# mpu6050schem.net
KiCad netlist of a schematic drawn in EAGLE
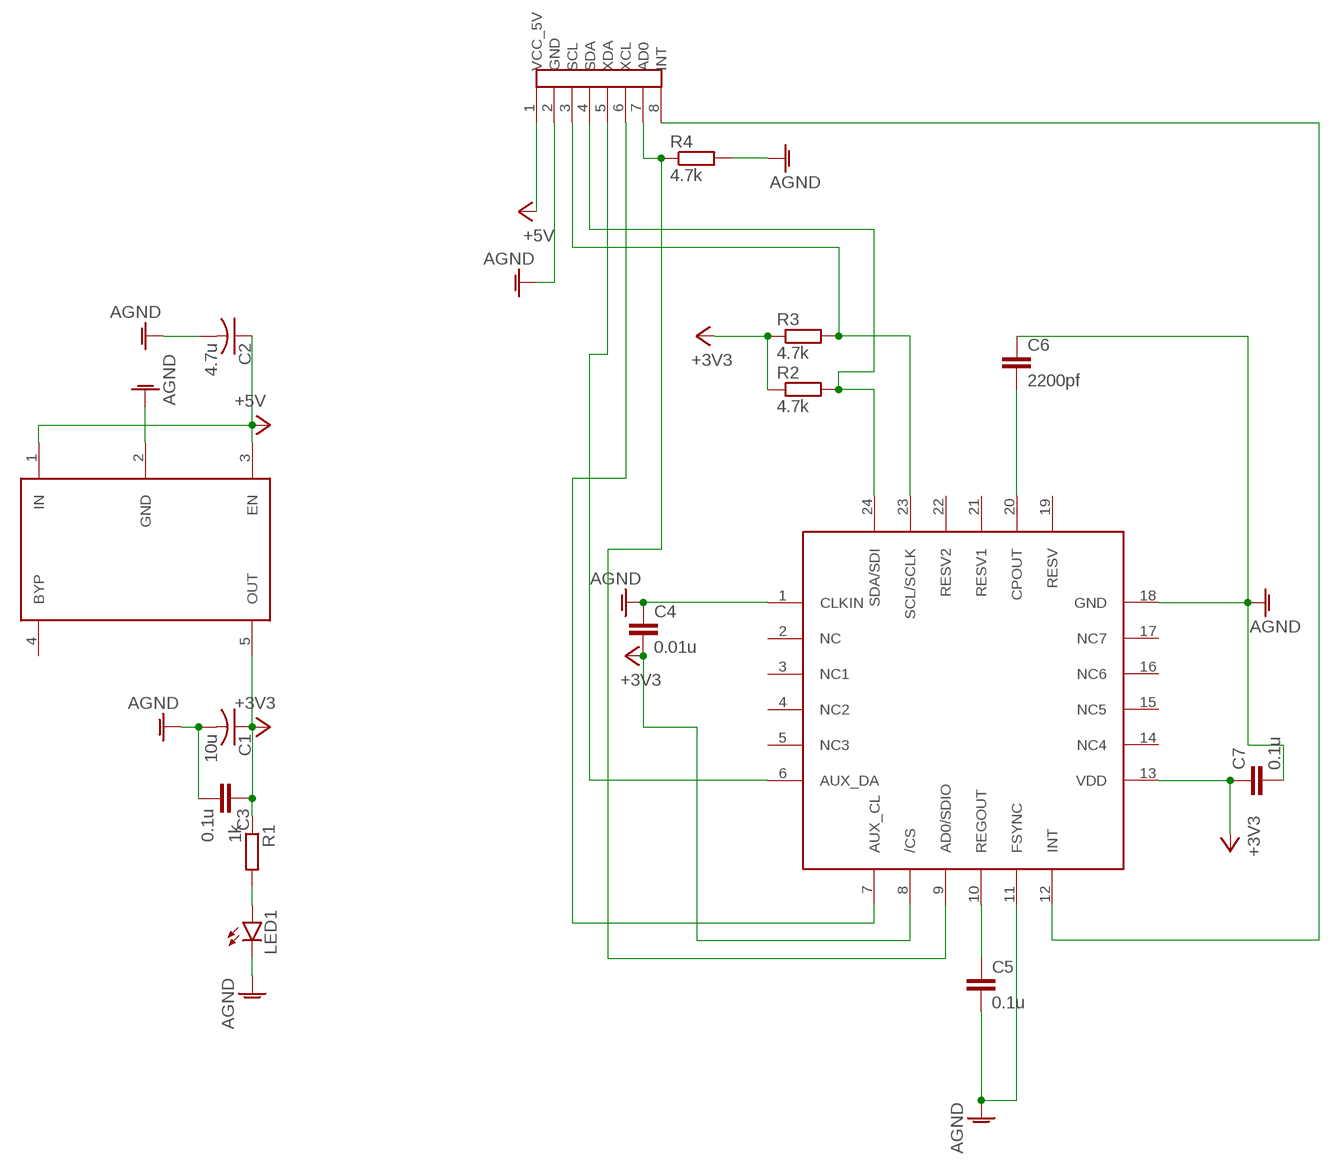
[diagram p0: schematic, sheet 1]

(export (version "E")
  (design (tool "Eeschema 10.0.6"))
  (components
    (comp (ref "C1")
      (value "10u")
      (footprint "eagle-import:C0603")
      (libsource (lib "eagle-import") (part "C-USC0603"))
    )
    (comp (ref "C2")
      (value "4.7u")
      (footprint "eagle-import:C0603")
      (libsource (lib "eagle-import") (part "C-USC0603"))
    )
    (comp (ref "C3")
      (value "0.1u")
      (footprint "eagle-import:C0402")
      (libsource (lib "eagle-import") (part "C-EUC0402"))
    )
    (comp (ref "C4")
      (value "0.01u")
      (footprint "eagle-import:C0402")
      (libsource (lib "eagle-import") (part "C-EUC0402"))
    )
    (comp (ref "C5")
      (value "0.1u")
      (footprint "eagle-import:C0402")
      (libsource (lib "eagle-import") (part "C-EUC0402"))
    )
    (comp (ref "C6")
      (value "2200pf")
      (footprint "eagle-import:C0402")
      (libsource (lib "eagle-import") (part "C-EUC0402"))
    )
    (comp (ref "C7")
      (value "0.1u")
      (footprint "eagle-import:C0402")
      (libsource (lib "eagle-import") (part "C-EUC0402"))
    )
    (comp (ref "LDO3.3V")
      (value "MIC5219")
      (footprint "eagle-import:SOT95P295X145-5N")
      (libsource (lib "eagle-import") (part "MIC5219"))
    )
    (comp (ref "LED1")
      (value "LEDCHIP-LED0603")
      (footprint "eagle-import:CHIP-LED0603")
      (libsource (lib "eagle-import") (part "LEDCHIP-LED0603"))
    )
    (comp (ref "R1")
      (value "1k")
      (footprint "eagle-import:R0402")
      (libsource (lib "eagle-import") (part "R-EU_R0402"))
    )
    (comp (ref "R2")
      (value "4.7k")
      (footprint "eagle-import:R0402")
      (libsource (lib "eagle-import") (part "R-EU_R0402"))
    )
    (comp (ref "R3")
      (value "4.7k")
      (footprint "eagle-import:R0402")
      (libsource (lib "eagle-import") (part "R-EU_R0402"))
    )
    (comp (ref "R4")
      (value "4.7k")
      (footprint "eagle-import:R0402")
      (libsource (lib "eagle-import") (part "R-EU_R0402"))
    )
    (comp (ref "U$1")
      (value "MPU6050")
      (footprint "eagle-import:QFN50P395X395X90-25T265X255N")
      (libsource (lib "eagle-import") (part "MPU6050"))
    )
    (comp (ref "U$2")
      (value "8PINSHEADER")
      (footprint "eagle-import:HDRRA8W64P254_1X8_2032X254X556B")
      (libsource (lib "eagle-import") (part "8PINSHEADER"))
    )
  )
  (nets
    (net (code "1") (name "+3V3") (class "Default")
      (node (ref "C1") (pin "1") (pinfunction "1_1") (pintype "passive"))
      (node (ref "C3") (pin "1") (pinfunction "1_1") (pintype "passive"))
      (node (ref "C4") (pin "2") (pinfunction "2_2") (pintype "passive"))
      (node (ref "C7") (pin "1") (pinfunction "1_1") (pintype "passive"))
      (node (ref "LDO3.3V") (pin "5") (pinfunction "OUT_5") (pintype "bidirectional"))
      (node (ref "R1") (pin "1") (pinfunction "1_1") (pintype "passive"))
      (node (ref "R2") (pin "1") (pinfunction "1_1") (pintype "passive"))
      (node (ref "R3") (pin "1") (pinfunction "1_1") (pintype "passive"))
      (node (ref "U$1") (pin "13") (pinfunction "VDD_13") (pintype "bidirectional"))
      (node (ref "U$1") (pin "8") (pinfunction "/CS_8") (pintype "bidirectional"))
    )
    (net (code "2") (name "+5V") (class "Default")
      (node (ref "C2") (pin "1") (pinfunction "1_1") (pintype "passive"))
      (node (ref "LDO3.3V") (pin "1") (pinfunction "IN_1") (pintype "bidirectional"))
      (node (ref "LDO3.3V") (pin "3") (pinfunction "EN_3") (pintype "bidirectional"))
      (node (ref "U$2") (pin "1") (pinfunction "VCC_5V_1") (pintype "bidirectional"))
    )
    (net (code "3") (name "AGND") (class "Default")
      (node (ref "C1") (pin "2") (pinfunction "2_2") (pintype "passive"))
      (node (ref "C2") (pin "2") (pinfunction "2_2") (pintype "passive"))
      (node (ref "C3") (pin "2") (pinfunction "2_2") (pintype "passive"))
      (node (ref "C4") (pin "1") (pinfunction "1_1") (pintype "passive"))
      (node (ref "C5") (pin "2") (pinfunction "2_2") (pintype "passive"))
      (node (ref "C6") (pin "1") (pinfunction "1_1") (pintype "passive"))
      (node (ref "C7") (pin "2") (pinfunction "2_2") (pintype "passive"))
      (node (ref "LDO3.3V") (pin "2") (pinfunction "GND_2") (pintype "bidirectional"))
      (node (ref "LED1") (pin "C") (pinfunction "C_C") (pintype "passive"))
      (node (ref "R4") (pin "2") (pinfunction "2_2") (pintype "passive"))
      (node (ref "U$1") (pin "1") (pinfunction "CLKIN_1") (pintype "bidirectional"))
      (node (ref "U$1") (pin "11") (pinfunction "FSYNC_11") (pintype "bidirectional"))
      (node (ref "U$1") (pin "18") (pinfunction "GND_18") (pintype "bidirectional"))
      (node (ref "U$2") (pin "2") (pinfunction "GND_2") (pintype "bidirectional"))
    )
    (net (code "4") (name "Net-(LED1-PadA)") (class "Default")
      (node (ref "LED1") (pin "A") (pinfunction "A_A") (pintype "passive"))
      (node (ref "R1") (pin "2") (pinfunction "2_2") (pintype "passive"))
    )
    (net (code "5") (name "Net-(U$1-AD0{slash}SDIO)") (class "Default")
      (node (ref "R4") (pin "1") (pinfunction "1_1") (pintype "passive"))
      (node (ref "U$1") (pin "9") (pinfunction "AD0/SDIO_9") (pintype "bidirectional"))
      (node (ref "U$2") (pin "7") (pinfunction "AD0_7") (pintype "bidirectional"))
    )
    (net (code "6") (name "Net-(U$1-AUX_CL)") (class "Default")
      (node (ref "U$1") (pin "7") (pinfunction "AUX_CL_7") (pintype "bidirectional"))
      (node (ref "U$2") (pin "6") (pinfunction "XCL_6") (pintype "bidirectional"))
    )
    (net (code "7") (name "Net-(U$1-AUX_DA)") (class "Default")
      (node (ref "U$1") (pin "6") (pinfunction "AUX_DA_6") (pintype "bidirectional"))
      (node (ref "U$2") (pin "5") (pinfunction "XDA_5") (pintype "bidirectional"))
    )
    (net (code "8") (name "Net-(U$1-CPOUT)") (class "Default")
      (node (ref "C6") (pin "2") (pinfunction "2_2") (pintype "passive"))
      (node (ref "U$1") (pin "20") (pinfunction "CPOUT_20") (pintype "bidirectional"))
    )
    (net (code "9") (name "Net-(U$1-INT)") (class "Default")
      (node (ref "U$1") (pin "12") (pinfunction "INT_12") (pintype "bidirectional"))
      (node (ref "U$2") (pin "8") (pinfunction "INT_8") (pintype "bidirectional"))
    )
    (net (code "10") (name "Net-(U$1-REGOUT)") (class "Default")
      (node (ref "C5") (pin "1") (pinfunction "1_1") (pintype "passive"))
      (node (ref "U$1") (pin "10") (pinfunction "REGOUT_10") (pintype "bidirectional"))
    )
    (net (code "11") (name "Net-(U$1-SCL{slash}SCLK)") (class "Default")
      (node (ref "R3") (pin "2") (pinfunction "2_2") (pintype "passive"))
      (node (ref "U$1") (pin "23") (pinfunction "SCL/SCLK_23") (pintype "bidirectional"))
      (node (ref "U$2") (pin "3") (pinfunction "SCL_3") (pintype "bidirectional"))
    )
    (net (code "12") (name "Net-(U$1-SDA{slash}SDI)") (class "Default")
      (node (ref "R2") (pin "2") (pinfunction "2_2") (pintype "passive"))
      (node (ref "U$1") (pin "24") (pinfunction "SDA/SDI_24") (pintype "bidirectional"))
      (node (ref "U$2") (pin "4") (pinfunction "SDA_4") (pintype "bidirectional"))
    )
    (net (code "13") (name "unconnected-(LDO3.3V-BYP-Pad4)") (class "Default")
      (node (ref "LDO3.3V") (pin "4") (pinfunction "BYP_4") (pintype "bidirectional"))
    )
    (net (code "14") (name "unconnected-(U$1-NC-Pad2)") (class "Default")
      (node (ref "U$1") (pin "2") (pinfunction "NC_2") (pintype "bidirectional"))
    )
    (net (code "15") (name "unconnected-(U$1-NC1-Pad3)") (class "Default")
      (node (ref "U$1") (pin "3") (pinfunction "NC1_3") (pintype "bidirectional"))
    )
    (net (code "16") (name "unconnected-(U$1-NC2-Pad4)") (class "Default")
      (node (ref "U$1") (pin "4") (pinfunction "NC2_4") (pintype "bidirectional"))
    )
    (net (code "17") (name "unconnected-(U$1-NC3-Pad5)") (class "Default")
      (node (ref "U$1") (pin "5") (pinfunction "NC3_5") (pintype "bidirectional"))
    )
    (net (code "18") (name "unconnected-(U$1-NC4-Pad14)") (class "Default")
      (node (ref "U$1") (pin "14") (pinfunction "NC4_14") (pintype "bidirectional"))
    )
    (net (code "19") (name "unconnected-(U$1-NC5-Pad15)") (class "Default")
      (node (ref "U$1") (pin "15") (pinfunction "NC5_15") (pintype "bidirectional"))
    )
    (net (code "20") (name "unconnected-(U$1-NC6-Pad16)") (class "Default")
      (node (ref "U$1") (pin "16") (pinfunction "NC6_16") (pintype "bidirectional"))
    )
    (net (code "21") (name "unconnected-(U$1-NC7-Pad17)") (class "Default")
      (node (ref "U$1") (pin "17") (pinfunction "NC7_17") (pintype "bidirectional"))
    )
    (net (code "22") (name "unconnected-(U$1-RESV-Pad19)") (class "Default")
      (node (ref "U$1") (pin "19") (pinfunction "RESV_19") (pintype "bidirectional"))
    )
    (net (code "23") (name "unconnected-(U$1-RESV1-Pad21)") (class "Default")
      (node (ref "U$1") (pin "21") (pinfunction "RESV1_21") (pintype "bidirectional"))
    )
    (net (code "24") (name "unconnected-(U$1-RESV2-Pad22)") (class "Default")
      (node (ref "U$1") (pin "22") (pinfunction "RESV2_22") (pintype "bidirectional"))
    )
  )
)
